# main_connector.net
KiCad netlist of a schematic drawn in Altium Designer
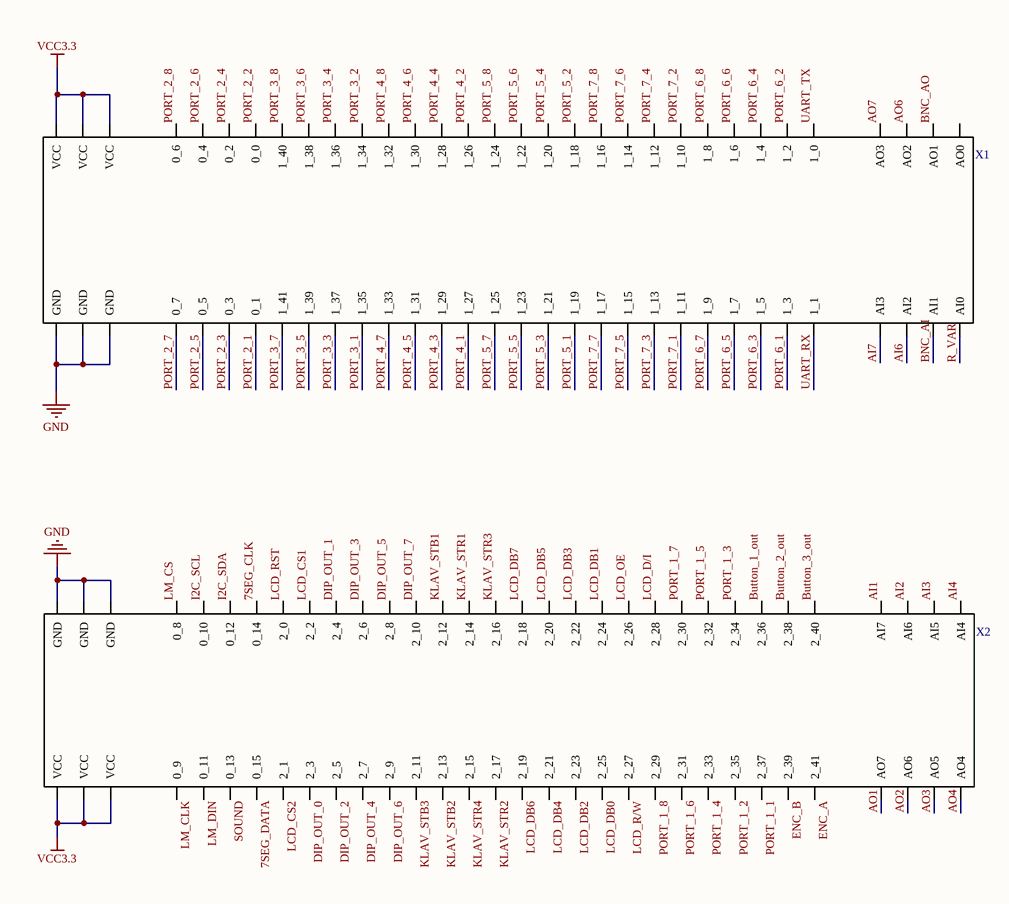
[diagram p0: main_connector.SchDoc]

(export (version "E")
  (design (tool "Eeschema 10.0.6"))
  (components
    (comp (ref "X1")
      (value "CONNECTOR_TOP")
      (footprint "Connector")
      (description "control board connector")
      (libsource (lib "elvis_lib") (part "CONNECTOR_TOP"))
    )
    (comp (ref "X2")
      (value "CONNECTOR_BOTTOM")
      (footprint "Connector")
      (description "control board connector")
      (libsource (lib "elvis_lib") (part "CONNECTOR_BOTTOM"))
    )
  )
  (nets
    (net (code "1") (name "/7SEG_CLK") (class "Default")
      (node (ref "X2") (pin "6") (pinfunction "0_14_6") (pintype "passive"))
    )
    (net (code "2") (name "/7SEG_DATA") (class "Default")
      (node (ref "X2") (pin "57") (pinfunction "0_15_57") (pintype "passive"))
    )
    (net (code "3") (name "/AI1") (class "Default")
      (node (ref "X2") (pin "28") (pinfunction "AI7_28") (pintype "passive"))
    )
    (net (code "4") (name "/AI2") (class "Default")
      (node (ref "X2") (pin "29") (pinfunction "AI6_29") (pintype "passive"))
    )
    (net (code "5") (name "/AI3") (class "Default")
      (node (ref "X2") (pin "30") (pinfunction "AI5_30") (pintype "passive"))
    )
    (net (code "6") (name "/AI4") (class "Default")
      (node (ref "X2") (pin "31") (pinfunction "AI4_31") (pintype "passive"))
    )
    (net (code "7") (name "/AI6") (class "Default")
      (node (ref "X1") (pin "34") (pinfunction "AI2_34") (pintype "passive"))
    )
    (net (code "8") (name "/AI7") (class "Default")
      (node (ref "X1") (pin "35") (pinfunction "AI3_35") (pintype "passive"))
    )
    (net (code "9") (name "/AO1") (class "Default")
      (node (ref "X2") (pin "35") (pinfunction "AO7_35") (pintype "passive"))
    )
    (net (code "10") (name "/AO2") (class "Default")
      (node (ref "X2") (pin "34") (pinfunction "AO6_34") (pintype "passive"))
    )
    (net (code "11") (name "/AO3") (class "Default")
      (node (ref "X2") (pin "33") (pinfunction "AO5_33") (pintype "passive"))
    )
    (net (code "12") (name "/AO4") (class "Default")
      (node (ref "X2") (pin "32") (pinfunction "AO4_32") (pintype "passive"))
    )
    (net (code "13") (name "/AO6") (class "Default")
      (node (ref "X1") (pin "29") (pinfunction "AO2_29") (pintype "passive"))
    )
    (net (code "14") (name "/AO7") (class "Default")
      (node (ref "X1") (pin "28") (pinfunction "AO3_28") (pintype "passive"))
    )
    (net (code "15") (name "/BNC_AI") (class "Default")
      (node (ref "X1") (pin "33") (pinfunction "AI1_33") (pintype "passive"))
    )
    (net (code "16") (name "/BNC_AO") (class "Default")
      (node (ref "X1") (pin "30") (pinfunction "AO1_30") (pintype "passive"))
    )
    (net (code "17") (name "/Button_1_out") (class "Default")
      (node (ref "X2") (pin "25") (pinfunction "2_36_25") (pintype "passive"))
    )
    (net (code "18") (name "/Button_2_out") (class "Default")
      (node (ref "X2") (pin "26") (pinfunction "2_38_26") (pintype "passive"))
    )
    (net (code "19") (name "/Button_3_out") (class "Default")
      (node (ref "X2") (pin "27") (pinfunction "2_40_27") (pintype "passive"))
    )
    (net (code "20") (name "/DIP_OUT_0") (class "Default")
      (node (ref "X2") (pin "55") (pinfunction "2_3_55") (pintype "passive"))
    )
    (net (code "21") (name "/DIP_OUT_1") (class "Default")
      (node (ref "X2") (pin "9") (pinfunction "2_4_9") (pintype "passive"))
    )
    (net (code "22") (name "/DIP_OUT_2") (class "Default")
      (node (ref "X2") (pin "54") (pinfunction "2_5_54") (pintype "passive"))
    )
    (net (code "23") (name "/DIP_OUT_3") (class "Default")
      (node (ref "X2") (pin "10") (pinfunction "2_6_10") (pintype "passive"))
    )
    (net (code "24") (name "/DIP_OUT_4") (class "Default")
      (node (ref "X2") (pin "53") (pinfunction "2_7_53") (pintype "passive"))
    )
    (net (code "25") (name "/DIP_OUT_5") (class "Default")
      (node (ref "X2") (pin "11") (pinfunction "2_8_11") (pintype "passive"))
    )
    (net (code "26") (name "/DIP_OUT_6") (class "Default")
      (node (ref "X2") (pin "52") (pinfunction "2_9_52") (pintype "passive"))
    )
    (net (code "27") (name "/DIP_OUT_7") (class "Default")
      (node (ref "X2") (pin "12") (pinfunction "2_10_12") (pintype "passive"))
    )
    (net (code "28") (name "/ENC_A") (class "Default")
      (node (ref "X2") (pin "36") (pinfunction "2_41_36") (pintype "passive"))
    )
    (net (code "29") (name "/ENC_B") (class "Default")
      (node (ref "X2") (pin "37") (pinfunction "2_39_37") (pintype "passive"))
    )
    (net (code "30") (name "/I2C_SCL") (class "Default")
      (node (ref "X2") (pin "4") (pinfunction "0_10_4") (pintype "passive"))
    )
    (net (code "31") (name "/I2C_SDA") (class "Default")
      (node (ref "X2") (pin "5") (pinfunction "0_12_5") (pintype "passive"))
    )
    (net (code "32") (name "/KLAV_STB1") (class "Default")
      (node (ref "X2") (pin "13") (pinfunction "2_12_13") (pintype "passive"))
    )
    (net (code "33") (name "/KLAV_STB2") (class "Default")
      (node (ref "X2") (pin "50") (pinfunction "2_13_50") (pintype "passive"))
    )
    (net (code "34") (name "/KLAV_STB3") (class "Default")
      (node (ref "X2") (pin "51") (pinfunction "2_11_51") (pintype "passive"))
    )
    (net (code "35") (name "/KLAV_STR1") (class "Default")
      (node (ref "X2") (pin "14") (pinfunction "2_14_14") (pintype "passive"))
    )
    (net (code "36") (name "/KLAV_STR2") (class "Default")
      (node (ref "X2") (pin "48") (pinfunction "2_17_48") (pintype "passive"))
    )
    (net (code "37") (name "/KLAV_STR3") (class "Default")
      (node (ref "X2") (pin "15") (pinfunction "2_16_15") (pintype "passive"))
    )
    (net (code "38") (name "/KLAV_STR4") (class "Default")
      (node (ref "X2") (pin "49") (pinfunction "2_15_49") (pintype "passive"))
    )
    (net (code "39") (name "/LCD_CS1") (class "Default")
      (node (ref "X2") (pin "8") (pinfunction "2_2_8") (pintype "passive"))
    )
    (net (code "40") (name "/LCD_CS2") (class "Default")
      (node (ref "X2") (pin "56") (pinfunction "2_1_56") (pintype "passive"))
    )
    (net (code "41") (name "/LCD_DB0") (class "Default")
      (node (ref "X2") (pin "44") (pinfunction "2_25_44") (pintype "passive"))
    )
    (net (code "42") (name "/LCD_DB1") (class "Default")
      (node (ref "X2") (pin "19") (pinfunction "2_24_19") (pintype "passive"))
    )
    (net (code "43") (name "/LCD_DB2") (class "Default")
      (node (ref "X2") (pin "45") (pinfunction "2_23_45") (pintype "passive"))
    )
    (net (code "44") (name "/LCD_DB3") (class "Default")
      (node (ref "X2") (pin "18") (pinfunction "2_22_18") (pintype "passive"))
    )
    (net (code "45") (name "/LCD_DB4") (class "Default")
      (node (ref "X2") (pin "46") (pinfunction "2_21_46") (pintype "passive"))
    )
    (net (code "46") (name "/LCD_DB5") (class "Default")
      (node (ref "X2") (pin "17") (pinfunction "2_20_17") (pintype "passive"))
    )
    (net (code "47") (name "/LCD_DB6") (class "Default")
      (node (ref "X2") (pin "47") (pinfunction "2_19_47") (pintype "passive"))
    )
    (net (code "48") (name "/LCD_DB7") (class "Default")
      (node (ref "X2") (pin "16") (pinfunction "2_18_16") (pintype "passive"))
    )
    (net (code "49") (name "/LCD_D{slash}I") (class "Default")
      (node (ref "X2") (pin "21") (pinfunction "2_28_21") (pintype "passive"))
    )
    (net (code "50") (name "/LCD_OE") (class "Default")
      (node (ref "X2") (pin "20") (pinfunction "2_26_20") (pintype "passive"))
    )
    (net (code "51") (name "/LCD_RST") (class "Default")
      (node (ref "X2") (pin "7") (pinfunction "2_0_7") (pintype "passive"))
    )
    (net (code "52") (name "/LCD_R{slash}W") (class "Default")
      (node (ref "X2") (pin "43") (pinfunction "2_27_43") (pintype "passive"))
    )
    (net (code "53") (name "/LM_CLK") (class "Default")
      (node (ref "X2") (pin "60") (pinfunction "0_9_60") (pintype "passive"))
    )
    (net (code "54") (name "/LM_CS") (class "Default")
      (node (ref "X2") (pin "3") (pinfunction "0_8_3") (pintype "passive"))
    )
    (net (code "55") (name "/LM_DIN") (class "Default")
      (node (ref "X2") (pin "59") (pinfunction "0_11_59") (pintype "passive"))
    )
    (net (code "56") (name "/PORT_1_1") (class "Default")
      (node (ref "X2") (pin "38") (pinfunction "2_37_38") (pintype "passive"))
    )
    (net (code "57") (name "/PORT_1_2") (class "Default")
      (node (ref "X2") (pin "39") (pinfunction "2_35_39") (pintype "passive"))
    )
    (net (code "58") (name "/PORT_1_3") (class "Default")
      (node (ref "X2") (pin "24") (pinfunction "2_34_24") (pintype "passive"))
    )
    (net (code "59") (name "/PORT_1_4") (class "Default")
      (node (ref "X2") (pin "40") (pinfunction "2_33_40") (pintype "passive"))
    )
    (net (code "60") (name "/PORT_1_5") (class "Default")
      (node (ref "X2") (pin "23") (pinfunction "2_32_23") (pintype "passive"))
    )
    (net (code "61") (name "/PORT_1_6") (class "Default")
      (node (ref "X2") (pin "41") (pinfunction "2_31_41") (pintype "passive"))
    )
    (net (code "62") (name "/PORT_1_7") (class "Default")
      (node (ref "X2") (pin "22") (pinfunction "2_30_22") (pintype "passive"))
    )
    (net (code "63") (name "/PORT_1_8") (class "Default")
      (node (ref "X2") (pin "42") (pinfunction "2_29_42") (pintype "passive"))
    )
    (net (code "64") (name "/PORT_2_1") (class "Default")
      (node (ref "X1") (pin "57") (pinfunction "0_1_57") (pintype "passive"))
    )
    (net (code "65") (name "/PORT_2_2") (class "Default")
      (node (ref "X1") (pin "6") (pinfunction "0_0_6") (pintype "passive"))
    )
    (net (code "66") (name "/PORT_2_3") (class "Default")
      (node (ref "X1") (pin "58") (pinfunction "0_3_58") (pintype "passive"))
    )
    (net (code "67") (name "/PORT_2_4") (class "Default")
      (node (ref "X1") (pin "5") (pinfunction "0_2_5") (pintype "passive"))
    )
    (net (code "68") (name "/PORT_2_5") (class "Default")
      (node (ref "X1") (pin "59") (pinfunction "0_5_59") (pintype "passive"))
    )
    (net (code "69") (name "/PORT_2_6") (class "Default")
      (node (ref "X1") (pin "4") (pinfunction "0_4_4") (pintype "passive"))
    )
    (net (code "70") (name "/PORT_2_7") (class "Default")
      (node (ref "X1") (pin "60") (pinfunction "0_7_60") (pintype "passive"))
    )
    (net (code "71") (name "/PORT_2_8") (class "Default")
      (node (ref "X1") (pin "3") (pinfunction "0_6_3") (pintype "passive"))
    )
    (net (code "72") (name "/PORT_3_1") (class "Default")
      (node (ref "X1") (pin "53") (pinfunction "1_35_53") (pintype "passive"))
    )
    (net (code "73") (name "/PORT_3_2") (class "Default")
      (node (ref "X1") (pin "10") (pinfunction "1_34_10") (pintype "passive"))
    )
    (net (code "74") (name "/PORT_3_3") (class "Default")
      (node (ref "X1") (pin "54") (pinfunction "1_37_54") (pintype "passive"))
    )
    (net (code "75") (name "/PORT_3_4") (class "Default")
      (node (ref "X1") (pin "9") (pinfunction "1_36_9") (pintype "passive"))
    )
    (net (code "76") (name "/PORT_3_5") (class "Default")
      (node (ref "X1") (pin "55") (pinfunction "1_39_55") (pintype "passive"))
    )
    (net (code "77") (name "/PORT_3_6") (class "Default")
      (node (ref "X1") (pin "8") (pinfunction "1_38_8") (pintype "passive"))
    )
    (net (code "78") (name "/PORT_3_7") (class "Default")
      (node (ref "X1") (pin "56") (pinfunction "1_41_56") (pintype "passive"))
    )
    (net (code "79") (name "/PORT_3_8") (class "Default")
      (node (ref "X1") (pin "7") (pinfunction "1_40_7") (pintype "passive"))
    )
    (net (code "80") (name "/PORT_4_1") (class "Default")
      (node (ref "X1") (pin "49") (pinfunction "1_27_49") (pintype "passive"))
    )
    (net (code "81") (name "/PORT_4_2") (class "Default")
      (node (ref "X1") (pin "14") (pinfunction "1_26_14") (pintype "passive"))
    )
    (net (code "82") (name "/PORT_4_3") (class "Default")
      (node (ref "X1") (pin "50") (pinfunction "1_29_50") (pintype "passive"))
    )
    (net (code "83") (name "/PORT_4_4") (class "Default")
      (node (ref "X1") (pin "13") (pinfunction "1_28_13") (pintype "passive"))
    )
    (net (code "84") (name "/PORT_4_5") (class "Default")
      (node (ref "X1") (pin "51") (pinfunction "1_31_51") (pintype "passive"))
    )
    (net (code "85") (name "/PORT_4_6") (class "Default")
      (node (ref "X1") (pin "12") (pinfunction "1_30_12") (pintype "passive"))
    )
    (net (code "86") (name "/PORT_4_7") (class "Default")
      (node (ref "X1") (pin "52") (pinfunction "1_33_52") (pintype "passive"))
    )
    (net (code "87") (name "/PORT_4_8") (class "Default")
      (node (ref "X1") (pin "11") (pinfunction "1_32_11") (pintype "passive"))
    )
    (net (code "88") (name "/PORT_5_1") (class "Default")
      (node (ref "X1") (pin "45") (pinfunction "1_19_45") (pintype "passive"))
    )
    (net (code "89") (name "/PORT_5_2") (class "Default")
      (node (ref "X1") (pin "18") (pinfunction "1_18_18") (pintype "passive"))
    )
    (net (code "90") (name "/PORT_5_3") (class "Default")
      (node (ref "X1") (pin "46") (pinfunction "1_21_46") (pintype "passive"))
    )
    (net (code "91") (name "/PORT_5_4") (class "Default")
      (node (ref "X1") (pin "17") (pinfunction "1_20_17") (pintype "passive"))
    )
    (net (code "92") (name "/PORT_5_5") (class "Default")
      (node (ref "X1") (pin "47") (pinfunction "1_23_47") (pintype "passive"))
    )
    (net (code "93") (name "/PORT_5_6") (class "Default")
      (node (ref "X1") (pin "16") (pinfunction "1_22_16") (pintype "passive"))
    )
    (net (code "94") (name "/PORT_5_7") (class "Default")
      (node (ref "X1") (pin "48") (pinfunction "1_25_48") (pintype "passive"))
    )
    (net (code "95") (name "/PORT_5_8") (class "Default")
      (node (ref "X1") (pin "15") (pinfunction "1_24_15") (pintype "passive"))
    )
    (net (code "96") (name "/PORT_6_1") (class "Default")
      (node (ref "X1") (pin "37") (pinfunction "1_3_37") (pintype "passive"))
    )
    (net (code "97") (name "/PORT_6_2") (class "Default")
      (node (ref "X1") (pin "26") (pinfunction "1_2_26") (pintype "passive"))
    )
    (net (code "98") (name "/PORT_6_3") (class "Default")
      (node (ref "X1") (pin "38") (pinfunction "1_5_38") (pintype "passive"))
    )
    (net (code "99") (name "/PORT_6_4") (class "Default")
      (node (ref "X1") (pin "25") (pinfunction "1_4_25") (pintype "passive"))
    )
    (net (code "100") (name "/PORT_6_5") (class "Default")
      (node (ref "X1") (pin "39") (pinfunction "1_7_39") (pintype "passive"))
    )
    (net (code "101") (name "/PORT_6_6") (class "Default")
      (node (ref "X1") (pin "24") (pinfunction "1_6_24") (pintype "passive"))
    )
    (net (code "102") (name "/PORT_6_7") (class "Default")
      (node (ref "X1") (pin "40") (pinfunction "1_9_40") (pintype "passive"))
    )
    (net (code "103") (name "/PORT_6_8") (class "Default")
      (node (ref "X1") (pin "23") (pinfunction "1_8_23") (pintype "passive"))
    )
    (net (code "104") (name "/PORT_7_1") (class "Default")
      (node (ref "X1") (pin "41") (pinfunction "1_11_41") (pintype "passive"))
    )
    (net (code "105") (name "/PORT_7_2") (class "Default")
      (node (ref "X1") (pin "22") (pinfunction "1_10_22") (pintype "passive"))
    )
    (net (code "106") (name "/PORT_7_3") (class "Default")
      (node (ref "X1") (pin "42") (pinfunction "1_13_42") (pintype "passive"))
    )
    (net (code "107") (name "/PORT_7_4") (class "Default")
      (node (ref "X1") (pin "21") (pinfunction "1_12_21") (pintype "passive"))
    )
    (net (code "108") (name "/PORT_7_5") (class "Default")
      (node (ref "X1") (pin "43") (pinfunction "1_15_43") (pintype "passive"))
    )
    (net (code "109") (name "/PORT_7_6") (class "Default")
      (node (ref "X1") (pin "20") (pinfunction "1_14_20") (pintype "passive"))
    )
    (net (code "110") (name "/PORT_7_7") (class "Default")
      (node (ref "X1") (pin "44") (pinfunction "1_17_44") (pintype "passive"))
    )
    (net (code "111") (name "/PORT_7_8") (class "Default")
      (node (ref "X1") (pin "19") (pinfunction "1_16_19") (pintype "passive"))
    )
    (net (code "112") (name "/R_VAR") (class "Default")
      (node (ref "X1") (pin "32") (pinfunction "AI0_32") (pintype "passive"))
    )
    (net (code "113") (name "/SOUND") (class "Default")
      (node (ref "X2") (pin "58") (pinfunction "0_13_58") (pintype "passive"))
    )
    (net (code "114") (name "/UART_RX") (class "Default")
      (node (ref "X1") (pin "36") (pinfunction "1_1_36") (pintype "passive"))
    )
    (net (code "115") (name "/UART_TX") (class "Default")
      (node (ref "X1") (pin "27") (pinfunction "1_0_27") (pintype "passive"))
    )
    (net (code "116") (name "GND") (class "Default")
      (node (ref "X1") (pin "61") (pinfunction "GND_61") (pintype "passive"))
      (node (ref "X1") (pin "62") (pinfunction "GND_62") (pintype "passive"))
      (node (ref "X1") (pin "63") (pinfunction "GND_63") (pintype "passive"))
      (node (ref "X2") (pin "0") (pinfunction "GND_0") (pintype "passive"))
      (node (ref "X2") (pin "1") (pinfunction "GND_1") (pintype "passive"))
      (node (ref "X2") (pin "2") (pinfunction "GND_2") (pintype "passive"))
    )
    (net (code "117") (name "VCC3.3") (class "Default")
      (node (ref "X1") (pin "0") (pinfunction "VCC_0") (pintype "passive"))
      (node (ref "X1") (pin "1") (pinfunction "VCC_1") (pintype "passive"))
      (node (ref "X1") (pin "2") (pinfunction "VCC_2") (pintype "passive"))
      (node (ref "X2") (pin "61") (pinfunction "VCC_61") (pintype "passive"))
      (node (ref "X2") (pin "62") (pinfunction "VCC_62") (pintype "passive"))
      (node (ref "X2") (pin "63") (pinfunction "VCC_63") (pintype "passive"))
    )
    (net (code "118") (name "unconnected-(X1-AO0-Pad31)") (class "Default")
      (node (ref "X1") (pin "31") (pinfunction "AO0_31") (pintype "passive"))
    )
  )
)
